# 10_JZ.net
KiCad netlist of a schematic drawn in EAGLE
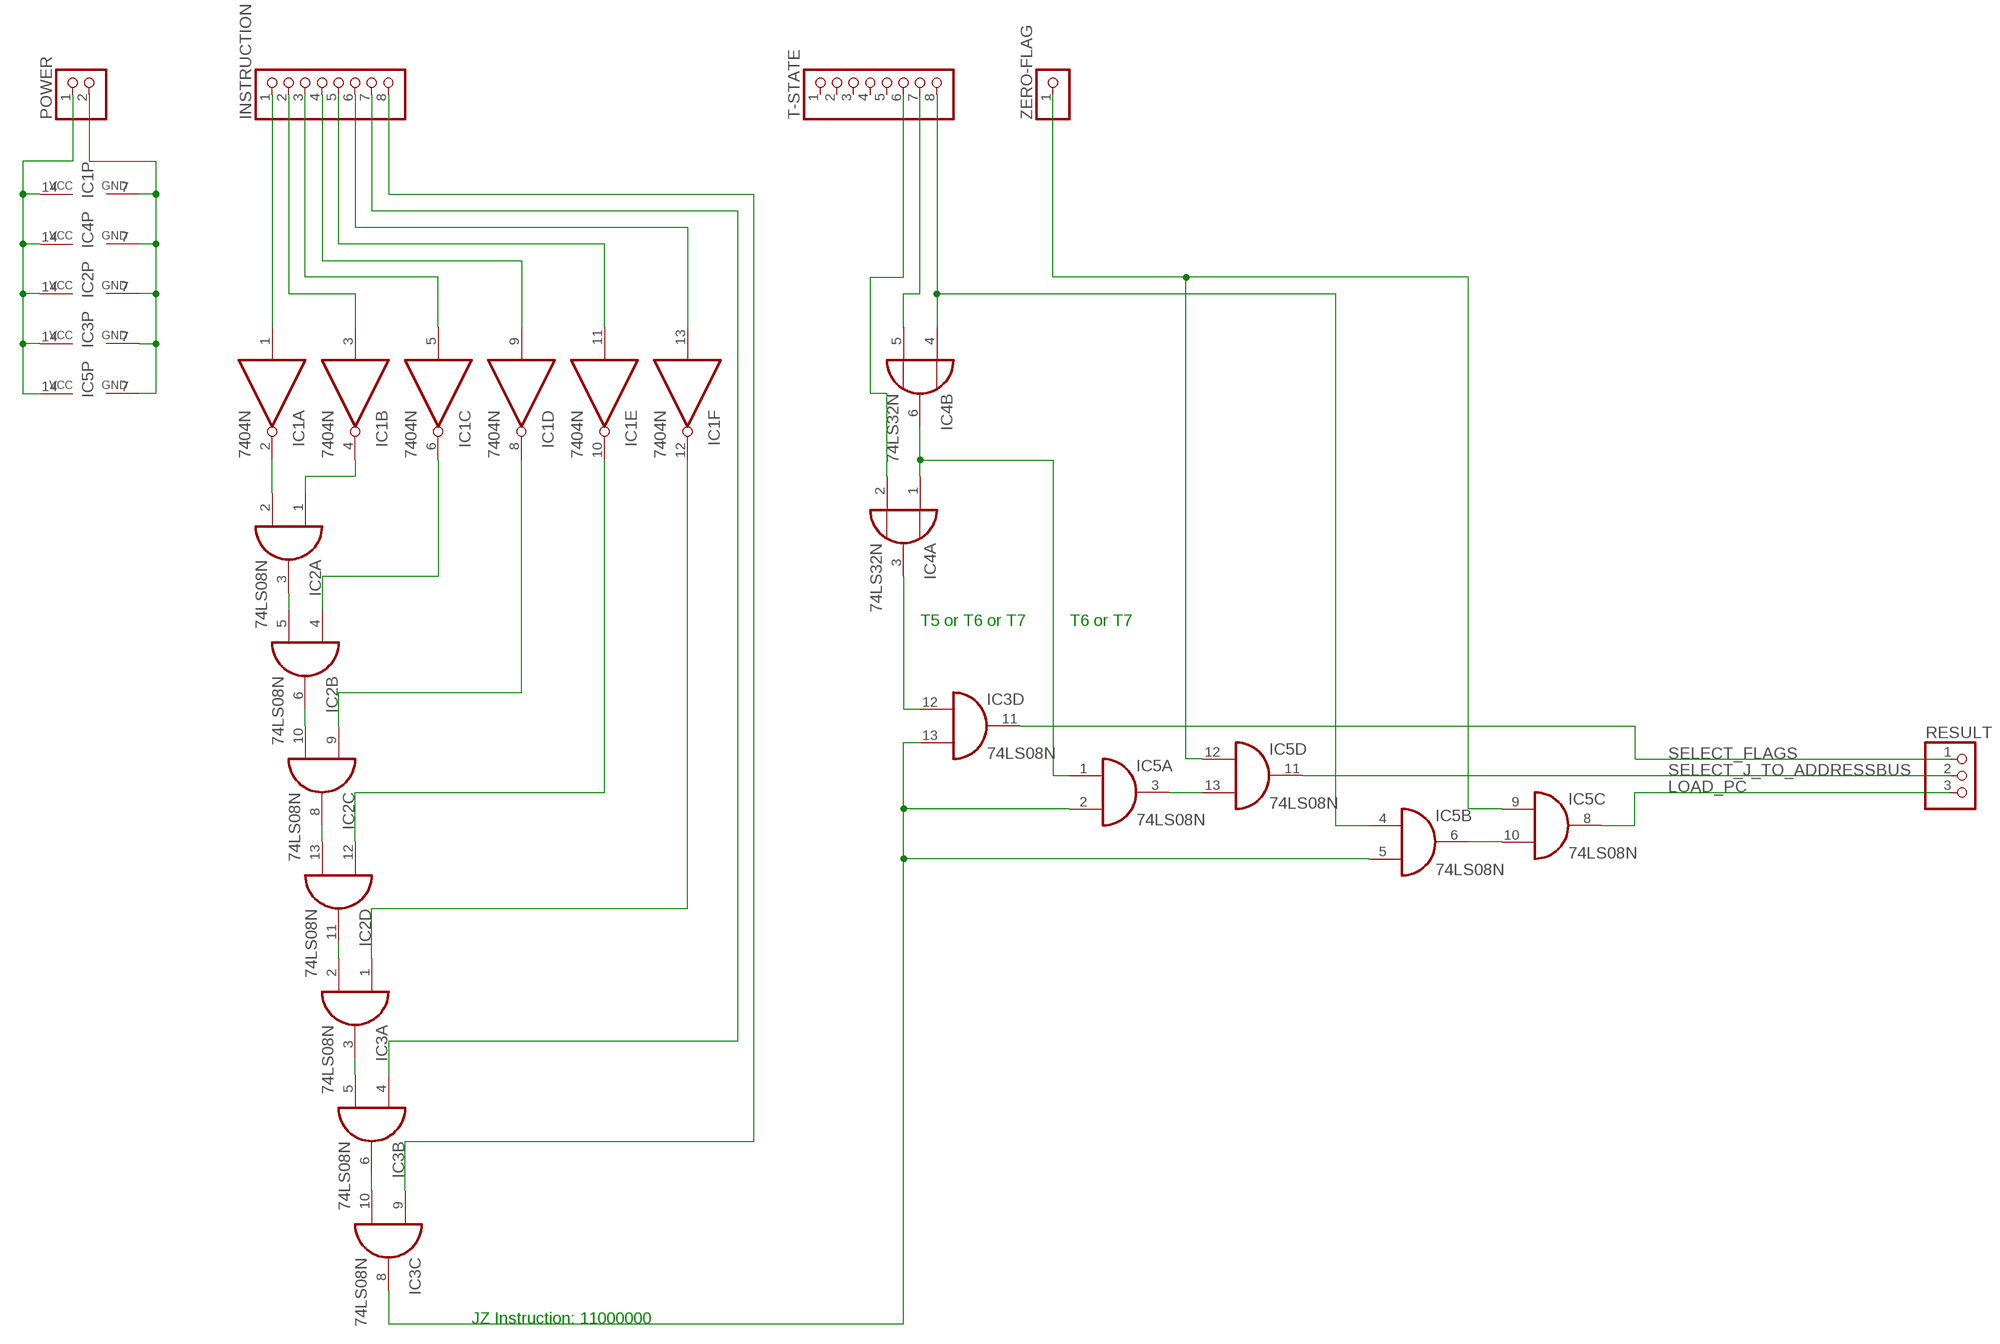
[diagram p0: schematic, sheet 1]

(export (version "E")
  (design (tool "Eeschema 10.0.6"))
  (components
    (comp (ref "IC1")
      (value "7404N")
      (footprint "eagle-import:DIL14")
      (libsource (lib "eagle-import") (part "7404N"))
    )
    (comp (ref "IC2")
      (value "74LS08N")
      (footprint "eagle-import:DIL14")
      (libsource (lib "eagle-import") (part "7408NLS"))
    )
    (comp (ref "IC3")
      (value "74LS08N")
      (footprint "eagle-import:DIL14")
      (libsource (lib "eagle-import") (part "7408NLS"))
    )
    (comp (ref "IC4")
      (value "74LS32N")
      (footprint "eagle-import:DIL14")
      (libsource (lib "eagle-import") (part "7432NLS"))
    )
    (comp (ref "IC5")
      (value "74LS08N")
      (footprint "eagle-import:DIL14")
      (libsource (lib "eagle-import") (part "7408NLS"))
    )
    (comp (ref "INSTRUCTION")
      (value "PINHD-1X8")
      (footprint "eagle-import:1X08")
      (libsource (lib "eagle-import") (part "PINHD-1X8"))
    )
    (comp (ref "POWER")
      (value "PINHD-1X2")
      (footprint "eagle-import:1X02")
      (libsource (lib "eagle-import") (part "PINHD-1X2"))
    )
    (comp (ref "RESULT")
      (value "PINHD-1X3")
      (footprint "eagle-import:1X03")
      (libsource (lib "eagle-import") (part "PINHD-1X3"))
    )
    (comp (ref "T-STATE")
      (value "PINHD-1X8")
      (footprint "eagle-import:1X08")
      (libsource (lib "eagle-import") (part "PINHD-1X8"))
    )
    (comp (ref "ZERO-FLAG")
      (value "PINHD-1X1")
      (footprint "eagle-import:1X01")
      (libsource (lib "eagle-import") (part "PINHD-1X1"))
    )
  )
  (nets
    (net (code "1") (name "/LOAD_PC") (class "Default")
      (node (ref "IC5") (pin "8") (pinfunction "O_8") (pintype "output"))
      (node (ref "RESULT") (pin "3") (pinfunction "3_3") (pintype "passive"))
    )
    (net (code "2") (name "/SELECT_FLAGS") (class "Default")
      (node (ref "IC3") (pin "11") (pinfunction "O_11") (pintype "output"))
      (node (ref "RESULT") (pin "1") (pinfunction "1_1") (pintype "passive"))
    )
    (net (code "3") (name "/SELECT_J_TO_ADDRESSBUS") (class "Default")
      (node (ref "IC5") (pin "11") (pinfunction "O_11") (pintype "output"))
      (node (ref "RESULT") (pin "2") (pinfunction "2_2") (pintype "passive"))
    )
    (net (code "4") (name "Net-(IC1A-I)") (class "Default")
      (node (ref "IC1") (pin "1") (pinfunction "I_1") (pintype "input"))
      (node (ref "INSTRUCTION") (pin "1") (pinfunction "1_1") (pintype "passive"))
    )
    (net (code "5") (name "Net-(IC1A-O)") (class "Default")
      (node (ref "IC1") (pin "2") (pinfunction "O_2") (pintype "output"))
      (node (ref "IC2") (pin "2") (pinfunction "I1_2") (pintype "input"))
    )
    (net (code "6") (name "Net-(IC1B-I)") (class "Default")
      (node (ref "IC1") (pin "3") (pinfunction "I_3") (pintype "input"))
      (node (ref "INSTRUCTION") (pin "2") (pinfunction "2_2") (pintype "passive"))
    )
    (net (code "7") (name "Net-(IC1B-O)") (class "Default")
      (node (ref "IC1") (pin "4") (pinfunction "O_4") (pintype "output"))
      (node (ref "IC2") (pin "1") (pinfunction "I0_1") (pintype "input"))
    )
    (net (code "8") (name "Net-(IC1C-I)") (class "Default")
      (node (ref "IC1") (pin "5") (pinfunction "I_5") (pintype "input"))
      (node (ref "INSTRUCTION") (pin "3") (pinfunction "3_3") (pintype "passive"))
    )
    (net (code "9") (name "Net-(IC1C-O)") (class "Default")
      (node (ref "IC1") (pin "6") (pinfunction "O_6") (pintype "output"))
      (node (ref "IC2") (pin "4") (pinfunction "I0_4") (pintype "input"))
    )
    (net (code "10") (name "Net-(IC1D-I)") (class "Default")
      (node (ref "IC1") (pin "9") (pinfunction "I_9") (pintype "input"))
      (node (ref "INSTRUCTION") (pin "4") (pinfunction "4_4") (pintype "passive"))
    )
    (net (code "11") (name "Net-(IC1D-O)") (class "Default")
      (node (ref "IC1") (pin "8") (pinfunction "O_8") (pintype "output"))
      (node (ref "IC2") (pin "9") (pinfunction "I0_9") (pintype "input"))
    )
    (net (code "12") (name "Net-(IC1E-I)") (class "Default")
      (node (ref "IC1") (pin "11") (pinfunction "I_11") (pintype "input"))
      (node (ref "INSTRUCTION") (pin "5") (pinfunction "5_5") (pintype "passive"))
    )
    (net (code "13") (name "Net-(IC1E-O)") (class "Default")
      (node (ref "IC1") (pin "10") (pinfunction "O_10") (pintype "output"))
      (node (ref "IC2") (pin "12") (pinfunction "I0_12") (pintype "input"))
    )
    (net (code "14") (name "Net-(IC1F-I)") (class "Default")
      (node (ref "IC1") (pin "13") (pinfunction "I_13") (pintype "input"))
      (node (ref "INSTRUCTION") (pin "6") (pinfunction "6_6") (pintype "passive"))
    )
    (net (code "15") (name "Net-(IC1F-O)") (class "Default")
      (node (ref "IC1") (pin "12") (pinfunction "O_12") (pintype "output"))
      (node (ref "IC3") (pin "1") (pinfunction "I0_1") (pintype "input"))
    )
    (net (code "16") (name "Net-(IC1G-GND)") (class "Default")
      (node (ref "IC1") (pin "7") (pinfunction "GND_7") (pintype "power_in"))
      (node (ref "IC2") (pin "7") (pinfunction "GND_7") (pintype "power_in"))
      (node (ref "IC3") (pin "7") (pinfunction "GND_7") (pintype "power_in"))
      (node (ref "IC4") (pin "7") (pinfunction "GND_7") (pintype "power_in"))
      (node (ref "IC5") (pin "7") (pinfunction "GND_7") (pintype "power_in"))
      (node (ref "POWER") (pin "2") (pinfunction "2_2") (pintype "passive"))
    )
    (net (code "17") (name "Net-(IC1G-VCC)") (class "Default")
      (node (ref "IC1") (pin "14") (pinfunction "VCC_14") (pintype "power_in"))
      (node (ref "IC2") (pin "14") (pinfunction "VCC_14") (pintype "power_in"))
      (node (ref "IC3") (pin "14") (pinfunction "VCC_14") (pintype "power_in"))
      (node (ref "IC4") (pin "14") (pinfunction "VCC_14") (pintype "power_in"))
      (node (ref "IC5") (pin "14") (pinfunction "VCC_14") (pintype "power_in"))
      (node (ref "POWER") (pin "1") (pinfunction "1_1") (pintype "passive"))
    )
    (net (code "18") (name "Net-(IC2A-O)") (class "Default")
      (node (ref "IC2") (pin "3") (pinfunction "O_3") (pintype "output"))
      (node (ref "IC2") (pin "5") (pinfunction "I1_5") (pintype "input"))
    )
    (net (code "19") (name "Net-(IC2B-O)") (class "Default")
      (node (ref "IC2") (pin "10") (pinfunction "I1_10") (pintype "input"))
      (node (ref "IC2") (pin "6") (pinfunction "O_6") (pintype "output"))
    )
    (net (code "20") (name "Net-(IC2C-O)") (class "Default")
      (node (ref "IC2") (pin "13") (pinfunction "I1_13") (pintype "input"))
      (node (ref "IC2") (pin "8") (pinfunction "O_8") (pintype "output"))
    )
    (net (code "21") (name "Net-(IC2D-O)") (class "Default")
      (node (ref "IC2") (pin "11") (pinfunction "O_11") (pintype "output"))
      (node (ref "IC3") (pin "2") (pinfunction "I1_2") (pintype "input"))
    )
    (net (code "22") (name "Net-(IC3A-O)") (class "Default")
      (node (ref "IC3") (pin "3") (pinfunction "O_3") (pintype "output"))
      (node (ref "IC3") (pin "5") (pinfunction "I1_5") (pintype "input"))
    )
    (net (code "23") (name "Net-(IC3B-I0)") (class "Default")
      (node (ref "IC3") (pin "4") (pinfunction "I0_4") (pintype "input"))
      (node (ref "INSTRUCTION") (pin "7") (pinfunction "7_7") (pintype "passive"))
    )
    (net (code "24") (name "Net-(IC3B-O)") (class "Default")
      (node (ref "IC3") (pin "10") (pinfunction "I1_10") (pintype "input"))
      (node (ref "IC3") (pin "6") (pinfunction "O_6") (pintype "output"))
    )
    (net (code "25") (name "Net-(IC3C-I0)") (class "Default")
      (node (ref "IC3") (pin "9") (pinfunction "I0_9") (pintype "input"))
      (node (ref "INSTRUCTION") (pin "8") (pinfunction "8_8") (pintype "passive"))
    )
    (net (code "26") (name "Net-(IC3C-O)") (class "Default")
      (node (ref "IC3") (pin "13") (pinfunction "I1_13") (pintype "input"))
      (node (ref "IC3") (pin "8") (pinfunction "O_8") (pintype "output"))
      (node (ref "IC5") (pin "2") (pinfunction "I1_2") (pintype "input"))
      (node (ref "IC5") (pin "5") (pinfunction "I1_5") (pintype "input"))
    )
    (net (code "27") (name "Net-(IC3D-I0)") (class "Default")
      (node (ref "IC3") (pin "12") (pinfunction "I0_12") (pintype "input"))
      (node (ref "IC4") (pin "3") (pinfunction "O_3") (pintype "output"))
    )
    (net (code "28") (name "Net-(IC4A-I0)") (class "Default")
      (node (ref "IC4") (pin "1") (pinfunction "I0_1") (pintype "input"))
      (node (ref "IC4") (pin "6") (pinfunction "O_6") (pintype "output"))
      (node (ref "IC5") (pin "1") (pinfunction "I0_1") (pintype "input"))
    )
    (net (code "29") (name "Net-(IC4A-I1)") (class "Default")
      (node (ref "IC4") (pin "2") (pinfunction "I1_2") (pintype "input"))
      (node (ref "T-STATE") (pin "6") (pinfunction "6_6") (pintype "passive"))
    )
    (net (code "30") (name "Net-(IC4B-I0)") (class "Default")
      (node (ref "IC4") (pin "4") (pinfunction "I0_4") (pintype "input"))
      (node (ref "IC5") (pin "4") (pinfunction "I0_4") (pintype "input"))
      (node (ref "T-STATE") (pin "8") (pinfunction "8_8") (pintype "passive"))
    )
    (net (code "31") (name "Net-(IC4B-I1)") (class "Default")
      (node (ref "IC4") (pin "5") (pinfunction "I1_5") (pintype "input"))
      (node (ref "T-STATE") (pin "7") (pinfunction "7_7") (pintype "passive"))
    )
    (net (code "32") (name "Net-(IC5A-O)") (class "Default")
      (node (ref "IC5") (pin "13") (pinfunction "I1_13") (pintype "input"))
      (node (ref "IC5") (pin "3") (pinfunction "O_3") (pintype "output"))
    )
    (net (code "33") (name "Net-(IC5B-O)") (class "Default")
      (node (ref "IC5") (pin "10") (pinfunction "I1_10") (pintype "input"))
      (node (ref "IC5") (pin "6") (pinfunction "O_6") (pintype "output"))
    )
    (net (code "34") (name "Net-(IC5C-I0)") (class "Default")
      (node (ref "IC5") (pin "12") (pinfunction "I0_12") (pintype "input"))
      (node (ref "IC5") (pin "9") (pinfunction "I0_9") (pintype "input"))
      (node (ref "ZERO-FLAG") (pin "1") (pinfunction "1_1") (pintype "passive"))
    )
    (net (code "35") (name "unconnected-(T-STATE-Pad1)") (class "Default")
      (node (ref "T-STATE") (pin "1") (pinfunction "1_1") (pintype "passive"))
    )
    (net (code "36") (name "unconnected-(T-STATE-Pad2)") (class "Default")
      (node (ref "T-STATE") (pin "2") (pinfunction "2_2") (pintype "passive"))
    )
    (net (code "37") (name "unconnected-(T-STATE-Pad3)") (class "Default")
      (node (ref "T-STATE") (pin "3") (pinfunction "3_3") (pintype "passive"))
    )
    (net (code "38") (name "unconnected-(T-STATE-Pad4)") (class "Default")
      (node (ref "T-STATE") (pin "4") (pinfunction "4_4") (pintype "passive"))
    )
    (net (code "39") (name "unconnected-(T-STATE-Pad5)") (class "Default")
      (node (ref "T-STATE") (pin "5") (pinfunction "5_5") (pintype "passive"))
    )
  )
)
